# 2_P2.net
KiCad netlist of a schematic drawn in Altium Designer
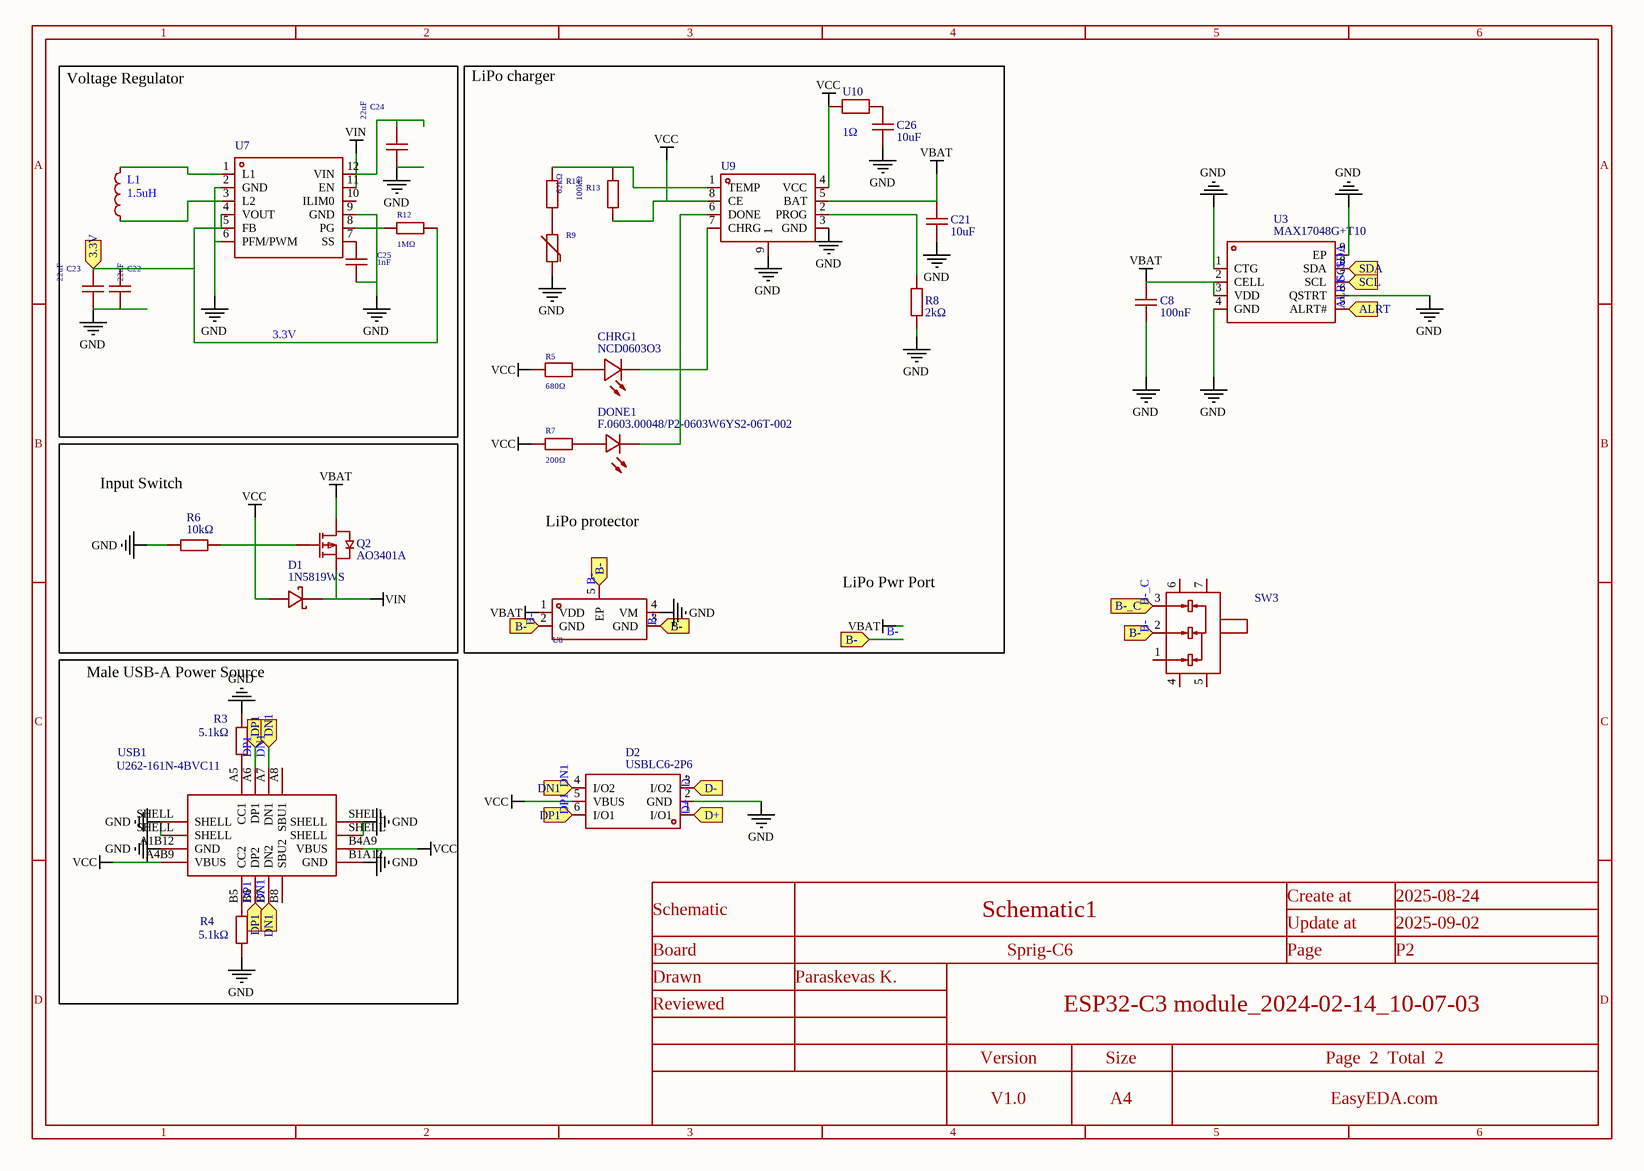
[diagram p0: 2_P2.schdoc]

(export (version "E")
  (design (tool "Eeschema 10.0.6"))
  (components
    (comp (ref "C8")
      (value "100nF")
      (footprint "C0402")
      (fields
        (field (name "MANUFACTURER") "FH(风华)")
        (field (name "MANUFACTURER PART") "0402B104K160NT")
        (field (name "TOLERANCE") "±10%")
      )
      (libsource (lib "altium-import") (part "root_1_0402B104K160NT_"))
    )
    (comp (ref "C21")
      (value "10uF")
      (footprint "C0402")
      (fields
        (field (name "MANUFACTURER") "SAMSUNG(三星)")
        (field (name "MANUFACTURER PART") "CL05A106MQ5NUNC")
        (field (name "TOLERANCE") "±20%")
      )
      (libsource (lib "altium-import") (part "root_1_CL05A106MQ5NUNC_"))
    )
    (comp (ref "C22")
      (value "22uF")
      (footprint "C0402")
      (fields
        (field (name "MANUFACTURER PART") "HGC0402R5226M6R3NTEJ")
        (field (name "MANUFACTURER") "Chinocera(华瓷)")
        (field (name "ALTIUM_VALUE") "22uF")
        (field (name "TOLERANCE") "±20%")
      )
      (libsource (lib "altium-import") (part "root_1_HGC0402R5226M6R3NTEJ_"))
    )
    (comp (ref "C23")
      (value "22uF")
      (footprint "C0402")
      (fields
        (field (name "MANUFACTURER PART") "HGC0402R5226M6R3NTEJ")
        (field (name "MANUFACTURER") "Chinocera(华瓷)")
        (field (name "ALTIUM_VALUE") "22uF")
        (field (name "TOLERANCE") "±20%")
      )
      (libsource (lib "altium-import") (part "root_1_HGC0402R5226M6R3NTEJ_"))
    )
    (comp (ref "C24")
      (value "22uF")
      (footprint "C0402")
      (fields
        (field (name "MANUFACTURER PART") "HGC0402R5226M6R3NTEJ")
        (field (name "MANUFACTURER") "Chinocera(华瓷)")
        (field (name "ALTIUM_VALUE") "22uF")
        (field (name "TOLERANCE") "±20%")
      )
      (libsource (lib "altium-import") (part "root_1_HGC0402R5226M6R3NTEJ_"))
    )
    (comp (ref "C25")
      (value "1nF")
      (footprint "C0402")
      (fields
        (field (name "MANUFACTURER") "YAGEO(国巨)")
        (field (name "MANUFACTURER PART") "CC0402KRX7R9BB102")
        (field (name "ALTIUM_VALUE") "1nF")
        (field (name "TOLERANCE") "±10%")
      )
      (libsource (lib "altium-import") (part "root_1_CC0402KRX7R9BB102_"))
    )
    (comp (ref "C26")
      (value "10uF")
      (footprint "C0402")
      (fields
        (field (name "MANUFACTURER") "SAMSUNG(三星)")
        (field (name "MANUFACTURER PART") "CL05A106MQ5NUNC")
        (field (name "TOLERANCE") "±20%")
      )
      (libsource (lib "altium-import") (part "root_1_CL05A106MQ5NUNC_"))
    )
    (comp (ref "CHRG1")
      (value "NCD0603O3")
      (footprint "LED0603-RD")
      (fields (field (name "MANUFACTURER") "国星光电"))
      (libsource (lib "altium-import") (part "root_2_NCD0603O3_"))
    )
    (comp (ref "D1")
      (value "1N5819WS")
      (footprint "SOD-323_L1.8-W1.3-LS2.5-RD")
      (fields (field (name "MANUFACTURER") "Hottech(合科泰)"))
      (libsource (lib "altium-import") (part "root_2_1N5819WS_C191023_"))
    )
    (comp (ref "D2")
      (value "USBLC6-2P6")
      (footprint "SOT-666-6_L1.6-W1.2-P0.50-LS1.6-BL")
      (fields (field (name "MANUFACTURER") "TECH PUBLIC(台舟)"))
      (libsource (lib "altium-import") (part "root_2_USBLC6-2P6_"))
    )
    (comp (ref "DONE1")
      (value "F.0603.00048/P2-0603W6YS2-06T-002")
      (footprint "LED-SMD_L1.6-W0.8-RD-WHITE-2")
      (fields (field (name "MANUFACTURER") "TUOZHAN(拓展光电)"))
      (libsource (lib "altium-import") (part "root_2_F.0603.00048/P2-0603W6YS2-06T-002_"))
    )
    (comp (ref "L1")
      (value "1.5uH")
      (footprint "L0806")
      (fields
        (field (name "MANUFACTURER") "muRata(村田)")
        (field (name "MANUFACTURER PART") "DFE201610E-1R5M=P2")
        (field (name "ALTIUM_VALUE") "1.5uH")
        (field (name "TOLERANCE") "±20%")
      )
      (libsource (lib "altium-import") (part "root_1_DFE201610E-1R5M=P2_"))
    )
    (comp (ref "Q2")
      (value "AO3401A")
      (footprint "SOT-23_L2.9-W1.3-P1.90-LS2.4-BR")
      (fields (field (name "MANUFACTURER") "AOS"))
      (libsource (lib "altium-import") (part "root_0_AO3401A_C15127_"))
    )
    (comp (ref "R3")
      (value "5.1kΩ")
      (footprint "R0402")
      (fields
        (field (name "MANUFACTURER") "UNI-ROYAL(厚声)")
        (field (name "MANUFACTURER PART") "0402WGJ0512TCE")
        (field (name "TOLERANCE") "±5%")
      )
      (libsource (lib "altium-import") (part "root_1_0402WGJ0512TCE_"))
    )
    (comp (ref "R4")
      (value "5.1kΩ")
      (footprint "R0402")
      (fields
        (field (name "MANUFACTURER") "UNI-ROYAL(厚声)")
        (field (name "MANUFACTURER PART") "0402WGJ0512TCE")
        (field (name "TOLERANCE") "±5%")
      )
      (libsource (lib "altium-import") (part "root_1_0402WGJ0512TCE_"))
    )
    (comp (ref "R5")
      (value "680Ω")
      (footprint "R0402")
      (fields
        (field (name "MANUFACTURER") "FH(风华)")
        (field (name "MANUFACTURER PART") "RC-02K681JT")
        (field (name "ALTIUM_VALUE") "680Ω")
        (field (name "TOLERANCE") "±5%")
      )
      (libsource (lib "altium-import") (part "root_0_RC-02K681JT_"))
    )
    (comp (ref "R6")
      (value "10kΩ")
      (footprint "R0402")
      (fields
        (field (name "MANUFACTURER") "大毅科技")
        (field (name "MANUFACTURER PART") "RMS04FT1002")
        (field (name "TOLERANCE") "±1%")
      )
      (libsource (lib "altium-import") (part "root_0_RMS04FT1002_"))
    )
    (comp (ref "R7")
      (value "200Ω")
      (footprint "R0402")
      (fields
        (field (name "MANUFACTURER") "UNI-ROYAL(厚声)")
        (field (name "MANUFACTURER PART") "0402WGF2000TCE")
        (field (name "ALTIUM_VALUE") "200Ω")
        (field (name "TOLERANCE") "±1%")
      )
      (libsource (lib "altium-import") (part "root_0_0402WGF2000TCE_"))
    )
    (comp (ref "R8")
      (value "2kΩ")
      (footprint "R0402")
      (fields
        (field (name "MANUFACTURER") "UNI-ROYAL(厚声)")
        (field (name "MANUFACTURER PART") "0402WGF2001TCE")
        (field (name "TOLERANCE") "±1%")
      )
      (libsource (lib "altium-import") (part "root_1_0402WGF2001TCE_"))
    )
    (comp (ref "R9")
      (value "FNTC0805X104F4250FB")
      (footprint "R0805")
      (fields (field (name "MANUFACTURER") "cjiang(长江微电)"))
      (libsource (lib "altium-import") (part "root_1_FNTC0805X104F4250FB_"))
    )
    (comp (ref "R12")
      (value "1MΩ")
      (footprint "R0402")
      (fields
        (field (name "MANUFACTURER") "UNI-ROYAL(厚声)")
        (field (name "MANUFACTURER PART") "0402WGF1004TCE")
        (field (name "ALTIUM_VALUE") "1MΩ")
        (field (name "TOLERANCE") "±1%")
      )
      (libsource (lib "altium-import") (part "root_0_0402WGF1004TCE_"))
    )
    (comp (ref "R13")
      (value "100kΩ")
      (footprint "R0402")
      (fields
        (field (name "MANUFACTURER") "UNI-ROYAL(厚声)")
        (field (name "MANUFACTURER PART") "0402WGF1003TCE")
        (field (name "ALTIUM_VALUE") "100kΩ")
        (field (name "TOLERANCE") "±1%")
      )
      (libsource (lib "altium-import") (part "root_1_0402WGF1003TCE_"))
    )
    (comp (ref "R14")
      (value "62kΩ")
      (footprint "R0402")
      (fields
        (field (name "MANUFACTURER") "PANASONIC(松下)")
        (field (name "MANUFACTURER PART") "ERJ2RKF6202X")
        (field (name "ALTIUM_VALUE") "62kΩ")
        (field (name "TOLERANCE") "±1%")
      )
      (libsource (lib "altium-import") (part "root_1_ERJ2RKF6202X_"))
    )
    (comp (ref "SW3")
      (value "MK-12C03-G015")
      (footprint "SW-SMD_MK-12C03-G015")
      (fields (field (name "MANUFACTURER") "G-Switch(品赞)"))
      (libsource (lib "altium-import") (part "root_1_MK-12C03-G015_"))
    )
    (comp (ref "U3")
      (value "MAX17048G+T10")
      (footprint "DFN-8_L2.0-W2.0-P0.50-BL-EP")
      (fields (field (name "MANUFACTURER") "ADI(亚德诺)/MAXIM(美信)"))
      (libsource (lib "altium-import") (part "root_0_MAX17048G+T10_"))
    )
    (comp (ref "U7")
      (value "TPS63051RMWR")
      (footprint "QFN-12_L2.5-W2.5-P0.50-TL")
      (fields (field (name "MANUFACTURER") "TI(德州仪器)"))
      (libsource (lib "altium-import") (part "root_0_TPS63051RMWR_"))
    )
    (comp (ref "U8")
      (value "AP6683")
      (footprint "DFN-4_L1.0-W1.0-P0.65-BL-EP")
      (fields (field (name "MANUFACTURER") "ALLPOWER(铨力)"))
      (libsource (lib "altium-import") (part "root_0_AP6683_"))
    )
    (comp (ref "U9")
      (value "LGS4056H")
      (footprint "DFN-8_L2.0-W2.0-P0.50-TL-EP1.6")
      (fields (field (name "MANUFACTURER") "Legend-Si(棱晶半导体)"))
      (libsource (lib "altium-import") (part "root_0_LGS4056H_"))
    )
    (comp (ref "U10")
      (value "1Ω")
      (footprint "R0402")
      (fields
        (field (name "MANUFACTURER") "FOJAN(富捷)")
        (field (name "MANUFACTURER PART") "FRC0402F1R00TS")
        (field (name "ALTIUM_VALUE") "1Ω")
        (field (name "TOLERANCE") "±1%")
      )
      (libsource (lib "altium-import") (part "root_0_FRC0402F1R00TS_"))
    )
    (comp (ref "USB1")
      (value "U262-161N-4BVC11")
      (footprint "USB-3.1-SMD_U262-161N-4BVC11")
      (fields (field (name "MANUFACTURER") "XKB Connectivity(中国星坤)"))
      (libsource (lib "altium-import") (part "root_0_U262-161N-4BVC11_"))
    )
  )
  (nets
    (net (code "1") (name "/3.3V") (class "Default")
      (node (ref "C22") (pin "2") (pinfunction "2_2") (pintype "passive"))
      (node (ref "C23") (pin "2") (pinfunction "2_2") (pintype "passive"))
      (node (ref "R12") (pin "2") (pinfunction "2_2") (pintype "passive"))
      (node (ref "U7") (pin "4") (pinfunction "VOUT_4") (pintype "passive"))
      (node (ref "U7") (pin "5") (pinfunction "FB_5") (pintype "passive"))
    )
    (net (code "2") (name "/ALRT") (class "Default")
      (node (ref "U3") (pin "5") (pinfunction "ALRT#_5") (pintype "passive"))
    )
    (net (code "3") (name "/B-") (class "Default")
      (node (ref "SW3") (pin "2") (pinfunction "2_2") (pintype "passive"))
      (node (ref "U8") (pin "2") (pinfunction "GND_2") (pintype "passive"))
      (node (ref "U8") (pin "3") (pinfunction "GND_3") (pintype "passive"))
      (node (ref "U8") (pin "5") (pinfunction "EP_5") (pintype "passive"))
    )
    (net (code "4") (name "/B-_C") (class "Default")
      (node (ref "SW3") (pin "3") (pinfunction "3_3") (pintype "passive"))
    )
    (net (code "5") (name "/D+") (class "Default")
      (node (ref "D2") (pin "1") (pinfunction "I/O1_1") (pintype "passive"))
    )
    (net (code "6") (name "/D-") (class "Default")
      (node (ref "D2") (pin "3") (pinfunction "I/O2_3") (pintype "passive"))
    )
    (net (code "7") (name "/DN1") (class "Default")
      (node (ref "D2") (pin "4") (pinfunction "I/O2_4") (pintype "passive"))
      (node (ref "USB1") (pin "A7") (pinfunction "DN1_A7") (pintype "passive"))
      (node (ref "USB1") (pin "B7") (pinfunction "DN2_B7") (pintype "passive"))
    )
    (net (code "8") (name "/DP1") (class "Default")
      (node (ref "D2") (pin "6") (pinfunction "I/O1_6") (pintype "passive"))
      (node (ref "USB1") (pin "A6") (pinfunction "DP1_A6") (pintype "passive"))
      (node (ref "USB1") (pin "B6") (pinfunction "DP2_B6") (pintype "passive"))
    )
    (net (code "9") (name "/SCL") (class "Default")
      (node (ref "U3") (pin "7") (pinfunction "SCL_7") (pintype "passive"))
    )
    (net (code "10") (name "/SDA") (class "Default")
      (node (ref "U3") (pin "8") (pinfunction "SDA_8") (pintype "passive"))
    )
    (net (code "11") (name "GND") (class "Default")
      (node (ref "C21") (pin "1") (pinfunction "1_1") (pintype "passive"))
      (node (ref "C22") (pin "1") (pinfunction "1_1") (pintype "passive"))
      (node (ref "C23") (pin "1") (pinfunction "1_1") (pintype "passive"))
      (node (ref "C24") (pin "1") (pinfunction "1_1") (pintype "passive"))
      (node (ref "C25") (pin "1") (pinfunction "1_1") (pintype "passive"))
      (node (ref "C26") (pin "1") (pinfunction "1_1") (pintype "passive"))
      (node (ref "C8") (pin "1") (pinfunction "1_1") (pintype "passive"))
      (node (ref "D2") (pin "2") (pinfunction "GND_2") (pintype "passive"))
      (node (ref "R3") (pin "2") (pinfunction "2_2") (pintype "passive"))
      (node (ref "R4") (pin "1") (pinfunction "1_1") (pintype "passive"))
      (node (ref "R6") (pin "1") (pinfunction "1_1") (pintype "passive"))
      (node (ref "R8") (pin "1") (pinfunction "1_1") (pintype "passive"))
      (node (ref "R9") (pin "1") (pinfunction "1_1") (pintype "passive"))
      (node (ref "U3") (pin "1") (pinfunction "CTG_1") (pintype "passive"))
      (node (ref "U3") (pin "4") (pinfunction "GND_4") (pintype "passive"))
      (node (ref "U3") (pin "6") (pinfunction "QSTRT_6") (pintype "passive"))
      (node (ref "U3") (pin "9") (pinfunction "EP_9") (pintype "passive"))
      (node (ref "U7") (pin "2") (pinfunction "GND_2") (pintype "passive"))
      (node (ref "U7") (pin "6") (pinfunction "PFM/PWM_6") (pintype "passive"))
      (node (ref "U7") (pin "9") (pinfunction "GND_9") (pintype "passive"))
      (node (ref "U8") (pin "4") (pinfunction "VM_4") (pintype "passive"))
      (node (ref "U9") (pin "3") (pinfunction "GND_3") (pintype "passive"))
      (node (ref "U9") (pin "9") (pinfunction "1_9") (pintype "passive"))
      (node (ref "USB1") (pin "A1B12") (pinfunction "GND_A1B12") (pintype "passive"))
      (node (ref "USB1") (pin "B1A12") (pinfunction "GND_B1A12") (pintype "passive"))
      (node (ref "USB1") (pin "SHELL") (pinfunction "SHELL_SHELL") (pintype "passive"))
    )
    (net (code "12") (name "Net-(C26-Pad2)") (class "Default")
      (node (ref "C26") (pin "2") (pinfunction "2_2") (pintype "passive"))
      (node (ref "U10") (pin "2") (pinfunction "2_2") (pintype "passive"))
    )
    (net (code "13") (name "Net-(CHRG1-A)") (class "Default")
      (node (ref "CHRG1") (pin "1") (pinfunction "A_1") (pintype "passive"))
      (node (ref "R5") (pin "2") (pinfunction "2_2") (pintype "passive"))
    )
    (net (code "14") (name "Net-(CHRG1-K)") (class "Default")
      (node (ref "CHRG1") (pin "2") (pinfunction "K_2") (pintype "passive"))
      (node (ref "U9") (pin "7") (pinfunction "CHRG_7") (pintype "passive"))
    )
    (net (code "15") (name "Net-(DONE1-+)") (class "Default")
      (node (ref "DONE1") (pin "1") (pinfunction "+_1") (pintype "passive"))
      (node (ref "R7") (pin "2") (pinfunction "2_2") (pintype "passive"))
    )
    (net (code "16") (name "Net-(DONE1--)") (class "Default")
      (node (ref "DONE1") (pin "2") (pinfunction "-_2") (pintype "passive"))
      (node (ref "U9") (pin "6") (pinfunction "DONE_6") (pintype "passive"))
    )
    (net (code "17") (name "Net-(R14-Pad1)") (class "Default")
      (node (ref "R14") (pin "1") (pinfunction "1_1") (pintype "passive"))
      (node (ref "R9") (pin "2") (pinfunction "2_2") (pintype "passive"))
    )
    (net (code "18") (name "Net-(U7-L1)") (class "Default")
      (node (ref "L1") (pin "2") (pinfunction "2_2") (pintype "passive"))
      (node (ref "U7") (pin "1") (pinfunction "L1_1") (pintype "passive"))
    )
    (net (code "19") (name "Net-(U7-L2)") (class "Default")
      (node (ref "L1") (pin "1") (pinfunction "1_1") (pintype "passive"))
      (node (ref "U7") (pin "3") (pinfunction "L2_3") (pintype "passive"))
    )
    (net (code "20") (name "Net-(U7-PG)") (class "Default")
      (node (ref "R12") (pin "1") (pinfunction "1_1") (pintype "passive"))
      (node (ref "U7") (pin "8") (pinfunction "PG_8") (pintype "passive"))
    )
    (net (code "21") (name "Net-(U7-SS)") (class "Default")
      (node (ref "C25") (pin "2") (pinfunction "2_2") (pintype "passive"))
      (node (ref "U7") (pin "7") (pinfunction "SS_7") (pintype "passive"))
    )
    (net (code "22") (name "Net-(U9-PROG)") (class "Default")
      (node (ref "R8") (pin "2") (pinfunction "2_2") (pintype "passive"))
      (node (ref "U9") (pin "2") (pinfunction "PROG_2") (pintype "passive"))
    )
    (net (code "23") (name "Net-(U9-TEMP)") (class "Default")
      (node (ref "R13") (pin "2") (pinfunction "2_2") (pintype "passive"))
      (node (ref "R14") (pin "2") (pinfunction "2_2") (pintype "passive"))
      (node (ref "U9") (pin "1") (pinfunction "TEMP_1") (pintype "passive"))
    )
    (net (code "24") (name "Net-(USB1-CC1)") (class "Default")
      (node (ref "R3") (pin "1") (pinfunction "1_1") (pintype "passive"))
      (node (ref "USB1") (pin "A5") (pinfunction "CC1_A5") (pintype "passive"))
    )
    (net (code "25") (name "Net-(USB1-CC2)") (class "Default")
      (node (ref "R4") (pin "2") (pinfunction "2_2") (pintype "passive"))
      (node (ref "USB1") (pin "B5") (pinfunction "CC2_B5") (pintype "passive"))
    )
    (net (code "26") (name "VBAT") (class "Default")
      (node (ref "C21") (pin "2") (pinfunction "2_2") (pintype "passive"))
      (node (ref "C8") (pin "2") (pinfunction "2_2") (pintype "passive"))
      (node (ref "Q2") (pin "3") (pinfunction "D_3") (pintype "passive"))
      (node (ref "U3") (pin "2") (pinfunction "CELL_2") (pintype "passive"))
      (node (ref "U3") (pin "3") (pinfunction "VDD_3") (pintype "passive"))
      (node (ref "U8") (pin "1") (pinfunction "VDD_1") (pintype "passive"))
      (node (ref "U9") (pin "5") (pinfunction "BAT_5") (pintype "passive"))
    )
    (net (code "27") (name "VCC") (class "Default")
      (node (ref "D1") (pin "2") (pinfunction "+_2") (pintype "passive"))
      (node (ref "D2") (pin "5") (pinfunction "VBUS_5") (pintype "passive"))
      (node (ref "Q2") (pin "1") (pinfunction "G_1") (pintype "passive"))
      (node (ref "R13") (pin "1") (pinfunction "1_1") (pintype "passive"))
      (node (ref "R5") (pin "1") (pinfunction "1_1") (pintype "passive"))
      (node (ref "R6") (pin "2") (pinfunction "2_2") (pintype "passive"))
      (node (ref "R7") (pin "1") (pinfunction "1_1") (pintype "passive"))
      (node (ref "U10") (pin "1") (pinfunction "1_1") (pintype "passive"))
      (node (ref "U9") (pin "4") (pinfunction "VCC_4") (pintype "passive"))
      (node (ref "U9") (pin "8") (pinfunction "CE_8") (pintype "passive"))
      (node (ref "USB1") (pin "A4B9") (pinfunction "VBUS_A4B9") (pintype "passive"))
      (node (ref "USB1") (pin "B4A9") (pinfunction "VBUS_B4A9") (pintype "passive"))
    )
    (net (code "28") (name "VIN") (class "Default")
      (node (ref "C24") (pin "2") (pinfunction "2_2") (pintype "passive"))
      (node (ref "D1") (pin "1") (pinfunction "-_1") (pintype "passive"))
      (node (ref "Q2") (pin "2") (pinfunction "S_2") (pintype "passive"))
      (node (ref "U7") (pin "11") (pinfunction "EN_11") (pintype "passive"))
      (node (ref "U7") (pin "12") (pinfunction "VIN_12") (pintype "passive"))
    )
    (net (code "29") (name "unconnected-(SW3-Pad1)") (class "Default")
      (node (ref "SW3") (pin "1") (pinfunction "1_1") (pintype "passive"))
    )
    (net (code "30") (name "unconnected-(SW3-Pad4)") (class "Default")
      (node (ref "SW3") (pin "4") (pinfunction "4_4") (pintype "passive"))
    )
    (net (code "31") (name "unconnected-(SW3-Pad5)") (class "Default")
      (node (ref "SW3") (pin "5") (pinfunction "5_5") (pintype "passive"))
    )
    (net (code "32") (name "unconnected-(SW3-Pad6)") (class "Default")
      (node (ref "SW3") (pin "6") (pinfunction "6_6") (pintype "passive"))
    )
    (net (code "33") (name "unconnected-(SW3-Pad7)") (class "Default")
      (node (ref "SW3") (pin "7") (pinfunction "7_7") (pintype "passive"))
    )
    (net (code "34") (name "unconnected-(U7-ILIM0-Pad10)") (class "Default")
      (node (ref "U7") (pin "10") (pinfunction "ILIM0_10") (pintype "passive"))
    )
    (net (code "35") (name "unconnected-(USB1-SBU1-PadA8)") (class "Default")
      (node (ref "USB1") (pin "A8") (pinfunction "SBU1_A8") (pintype "passive"))
    )
    (net (code "36") (name "unconnected-(USB1-SBU2-PadB8)") (class "Default")
      (node (ref "USB1") (pin "B8") (pinfunction "SBU2_B8") (pintype "passive"))
    )
  )
)
